# breakout_board.net
KiCad netlist of a schematic drawn in EAGLE
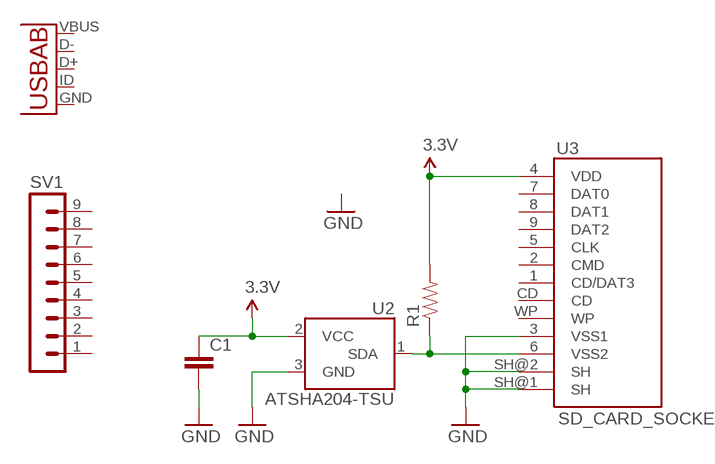
[diagram p0: schematic, sheet 1]

(export (version "E")
  (design (tool "Eeschema 10.0.6"))
  (components
    (comp (ref "C1")
      (value "C-EUC0402")
      (footprint "eagle-import:C0402")
      (libsource (lib "eagle-import") (part "C-EUC0402"))
    )
    (comp (ref "R1")
      (value "RESISTOR0603")
      (footprint "eagle-import:0603-RES")
      (libsource (lib "eagle-import") (part "RESISTOR0603"))
    )
    (comp (ref "SV1")
      (value "MA09-1")
      (footprint "eagle-import:MA09-1")
      (libsource (lib "eagle-import") (part "MA09-1"))
    )
    (comp (ref "U1")
      (value "USB-AB\"")
      (footprint "eagle-import:USB_AB_MICRO_1_1_V2")
      (libsource (lib "eagle-import") (part "USB-AB{dblquote}"))
    )
    (comp (ref "U2")
      (value "ATSHA204-TSU")
      (footprint "eagle-import:SOT23-3")
      (libsource (lib "eagle-import") (part "ATSHA204-TSU"))
    )
    (comp (ref "U3")
      (value "SD_CARD_SOCKET")
      (footprint "eagle-import:SD_1_1")
      (libsource (lib "eagle-import") (part "SD_CARD_SOCKET"))
    )
  )
  (nets
    (net (code "1") (name "3.3V") (class "Default")
      (node (ref "C1") (pin "1") (pinfunction "1_1") (pintype "passive"))
      (node (ref "R1") (pin "2") (pinfunction "2_2") (pintype "passive"))
      (node (ref "U2") (pin "2") (pinfunction "VCC_2") (pintype "bidirectional"))
      (node (ref "U3") (pin "4") (pinfunction "VDD_4") (pintype "power_in"))
    )
    (net (code "2") (name "GND") (class "Default")
      (node (ref "C1") (pin "2") (pinfunction "2_2") (pintype "passive"))
      (node (ref "U2") (pin "3") (pinfunction "GND_3") (pintype "bidirectional"))
      (node (ref "U3") (pin "3") (pinfunction "VSS1_3") (pintype "power_in"))
      (node (ref "U3") (pin "SH@1") (pinfunction "SH_SH@1") (pintype "bidirectional"))
      (node (ref "U3") (pin "SH@2") (pinfunction "SH_SH@2") (pintype "bidirectional"))
    )
    (net (code "3") (name "Net-(U2-SDA)") (class "Default")
      (node (ref "R1") (pin "1") (pinfunction "1_1") (pintype "passive"))
      (node (ref "U2") (pin "1") (pinfunction "SDA_1") (pintype "bidirectional"))
      (node (ref "U3") (pin "6") (pinfunction "VSS2_6") (pintype "power_in"))
    )
    (net (code "4") (name "unconnected-(SV1-Pad1)") (class "Default")
      (node (ref "SV1") (pin "1") (pinfunction "1_1") (pintype "passive"))
    )
    (net (code "5") (name "unconnected-(SV1-Pad2)") (class "Default")
      (node (ref "SV1") (pin "2") (pinfunction "2_2") (pintype "passive"))
    )
    (net (code "6") (name "unconnected-(SV1-Pad3)") (class "Default")
      (node (ref "SV1") (pin "3") (pinfunction "3_3") (pintype "passive"))
    )
    (net (code "7") (name "unconnected-(SV1-Pad4)") (class "Default")
      (node (ref "SV1") (pin "4") (pinfunction "4_4") (pintype "passive"))
    )
    (net (code "8") (name "unconnected-(SV1-Pad5)") (class "Default")
      (node (ref "SV1") (pin "5") (pinfunction "5_5") (pintype "passive"))
    )
    (net (code "9") (name "unconnected-(SV1-Pad6)") (class "Default")
      (node (ref "SV1") (pin "6") (pinfunction "6_6") (pintype "passive"))
    )
    (net (code "10") (name "unconnected-(SV1-Pad7)") (class "Default")
      (node (ref "SV1") (pin "7") (pinfunction "7_7") (pintype "passive"))
    )
    (net (code "11") (name "unconnected-(SV1-Pad8)") (class "Default")
      (node (ref "SV1") (pin "8") (pinfunction "8_8") (pintype "passive"))
    )
    (net (code "12") (name "unconnected-(SV1-Pad9)") (class "Default")
      (node (ref "SV1") (pin "9") (pinfunction "9_9") (pintype "passive"))
    )
    (net (code "13") (name "unconnected-(U1-PadD+)") (class "Default")
      (node (ref "U1") (pin "D+") (pinfunction "D+_D+") (pintype "bidirectional"))
    )
    (net (code "14") (name "unconnected-(U1-PadD-)") (class "Default")
      (node (ref "U1") (pin "D-") (pinfunction "D-_D-") (pintype "bidirectional"))
    )
    (net (code "15") (name "unconnected-(U1-PadGND)") (class "Default")
      (node (ref "U1") (pin "GND") (pinfunction "GND_GND") (pintype "bidirectional"))
    )
    (net (code "16") (name "unconnected-(U1-PadVBUS)") (class "Default")
      (node (ref "U1") (pin "VBUS") (pinfunction "VBUS_VBUS") (pintype "bidirectional"))
    )
    (net (code "17") (name "unconnected-(U1-USBID-PadID)") (class "Default")
      (node (ref "U1") (pin "ID") (pinfunction "USBID_ID") (pintype "bidirectional"))
    )
    (net (code "18") (name "unconnected-(U3-CD{slash}DAT3-Pad1)") (class "Default")
      (node (ref "U3") (pin "1") (pinfunction "CD/DAT3_1") (pintype "bidirectional"))
    )
    (net (code "19") (name "unconnected-(U3-CLK-Pad5)") (class "Default")
      (node (ref "U3") (pin "5") (pinfunction "CLK_5") (pintype "bidirectional"))
    )
    (net (code "20") (name "unconnected-(U3-CMD-Pad2)") (class "Default")
      (node (ref "U3") (pin "2") (pinfunction "CMD_2") (pintype "bidirectional"))
    )
    (net (code "21") (name "unconnected-(U3-DAT0-Pad7)") (class "Default")
      (node (ref "U3") (pin "7") (pinfunction "DAT0_7") (pintype "bidirectional"))
    )
    (net (code "22") (name "unconnected-(U3-DAT1-Pad8)") (class "Default")
      (node (ref "U3") (pin "8") (pinfunction "DAT1_8") (pintype "bidirectional"))
    )
    (net (code "23") (name "unconnected-(U3-DAT2-Pad9)") (class "Default")
      (node (ref "U3") (pin "9") (pinfunction "DAT2_9") (pintype "bidirectional"))
    )
    (net (code "24") (name "unconnected-(U3-PadCD)") (class "Default")
      (node (ref "U3") (pin "CD") (pinfunction "CD_CD") (pintype "bidirectional"))
    )
    (net (code "25") (name "unconnected-(U3-PadWP)") (class "Default")
      (node (ref "U3") (pin "WP") (pinfunction "WP_WP") (pintype "bidirectional"))
    )
  )
)
